# SCH_GloK_easyeda.net
KiCad netlist of a schematic drawn in EasyEDA
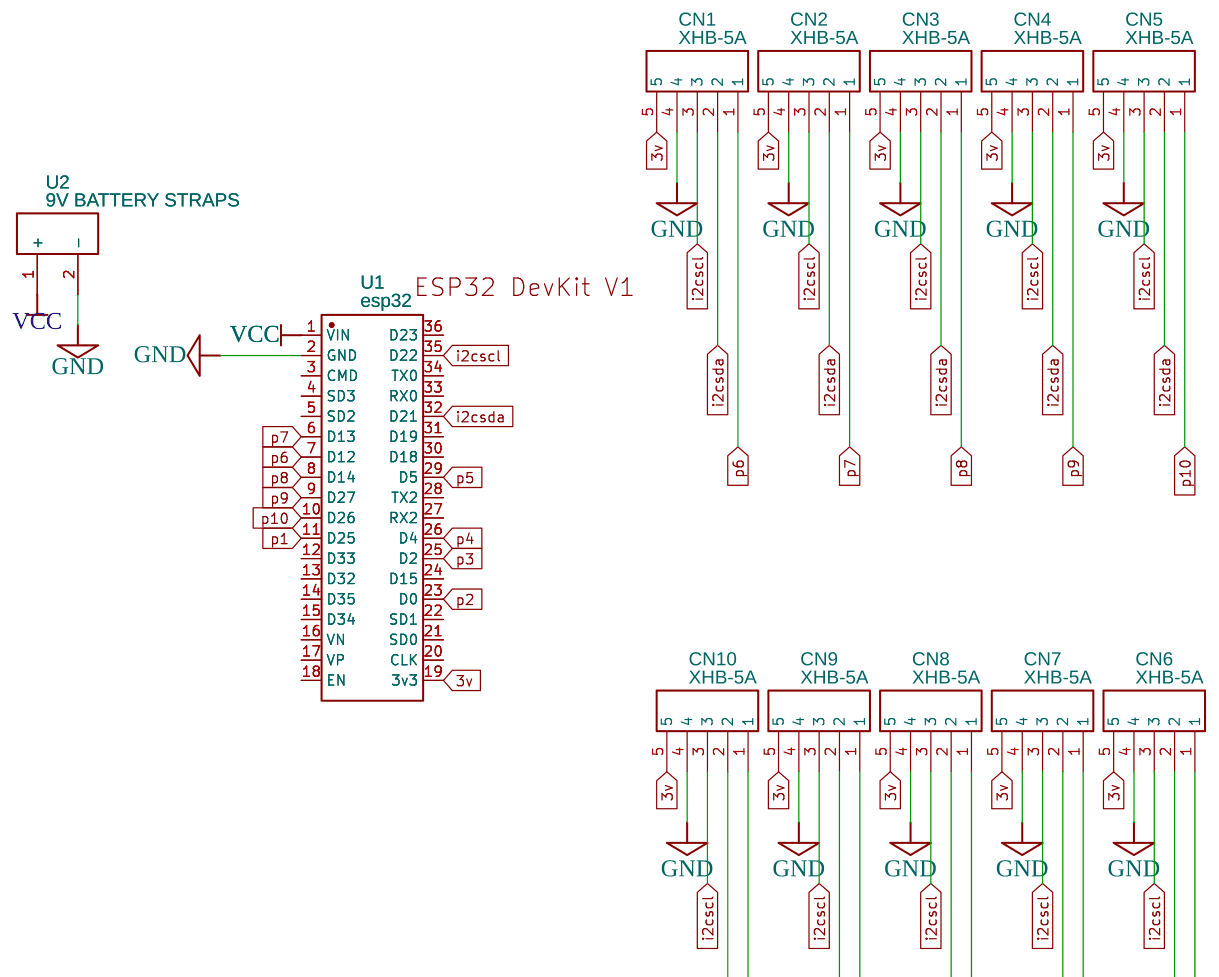
[diagram p0: schematic sheet]

(export (version "E")
  (design (tool "Eeschema 10.0.6"))
  (components
    (comp (ref "CN1")
      (value "XHB-5A")
      (fields (field (name "BOM_Supplier Part") "C66559"))
      (libsource (lib "") (part "XHB-5A"))
    )
    (comp (ref "CN2")
      (value "XHB-5A")
      (fields (field (name "BOM_Supplier Part") "C66559"))
      (libsource (lib "") (part "XHB-5A"))
    )
    (comp (ref "CN3")
      (value "XHB-5A")
      (fields (field (name "BOM_Supplier Part") "C66559"))
      (libsource (lib "") (part "XHB-5A"))
    )
    (comp (ref "CN4")
      (value "XHB-5A")
      (fields (field (name "BOM_Supplier Part") "C66559"))
      (libsource (lib "") (part "XHB-5A"))
    )
    (comp (ref "CN5")
      (value "XHB-5A")
      (fields (field (name "BOM_Supplier Part") "C66559"))
      (libsource (lib "") (part "XHB-5A"))
    )
    (comp (ref "CN6")
      (value "XHB-5A")
      (fields (field (name "BOM_Supplier Part") "C66559"))
      (libsource (lib "") (part "XHB-5A"))
    )
    (comp (ref "CN7")
      (value "XHB-5A")
      (fields (field (name "BOM_Supplier Part") "C66559"))
      (libsource (lib "") (part "XHB-5A"))
    )
    (comp (ref "CN8")
      (value "XHB-5A")
      (fields (field (name "BOM_Supplier Part") "C66559"))
      (libsource (lib "") (part "XHB-5A"))
    )
    (comp (ref "CN9")
      (value "XHB-5A")
      (fields (field (name "BOM_Supplier Part") "C66559"))
      (libsource (lib "") (part "XHB-5A"))
    )
    (comp (ref "CN10")
      (value "XHB-5A")
      (fields (field (name "BOM_Supplier Part") "C66559"))
      (libsource (lib "") (part "XHB-5A"))
    )
    (comp (ref "U1")
      (value "esp32")
      (fields (field (name "BOM_Supplier Part") "ESP32"))
      (libsource (lib "") (part "esp32"))
    )
    (comp (ref "U2")
      (value "9V BATTERY STRAPS")
      (fields (field (name "BOM_Manufacturer Part") "233") (field (name "BOM_Supplier Part") "36-233-ND"))
      (libsource (lib "") (part "9V BATTERY STRAPS"))
    )
  )
  (nets
    (net (code "1") (name "3v") (class "Default")
      (node (ref "CN1") (pin "5") (pinfunction "5_5") (pintype "unspecified"))
      (node (ref "CN10") (pin "5") (pinfunction "5_5") (pintype "unspecified"))
      (node (ref "CN2") (pin "5") (pinfunction "5_5") (pintype "unspecified"))
      (node (ref "CN3") (pin "5") (pinfunction "5_5") (pintype "unspecified"))
      (node (ref "CN4") (pin "5") (pinfunction "5_5") (pintype "unspecified"))
      (node (ref "CN5") (pin "5") (pinfunction "5_5") (pintype "unspecified"))
      (node (ref "CN6") (pin "5") (pinfunction "5_5") (pintype "unspecified"))
      (node (ref "CN7") (pin "5") (pinfunction "5_5") (pintype "unspecified"))
      (node (ref "CN8") (pin "5") (pinfunction "5_5") (pintype "unspecified"))
      (node (ref "CN9") (pin "5") (pinfunction "5_5") (pintype "unspecified"))
      (node (ref "U1") (pin "19") (pinfunction "3v3_19") (pintype "unspecified"))
    )
    (net (code "2") (name "GND") (class "Default")
      (node (ref "CN1") (pin "4") (pinfunction "4_4") (pintype "unspecified"))
      (node (ref "CN10") (pin "4") (pinfunction "4_4") (pintype "unspecified"))
      (node (ref "CN2") (pin "4") (pinfunction "4_4") (pintype "unspecified"))
      (node (ref "CN3") (pin "4") (pinfunction "4_4") (pintype "unspecified"))
      (node (ref "CN4") (pin "4") (pinfunction "4_4") (pintype "unspecified"))
      (node (ref "CN5") (pin "4") (pinfunction "4_4") (pintype "unspecified"))
      (node (ref "CN6") (pin "4") (pinfunction "4_4") (pintype "unspecified"))
      (node (ref "CN7") (pin "4") (pinfunction "4_4") (pintype "unspecified"))
      (node (ref "CN8") (pin "4") (pinfunction "4_4") (pintype "unspecified"))
      (node (ref "CN9") (pin "4") (pinfunction "4_4") (pintype "unspecified"))
      (node (ref "U1") (pin "2") (pinfunction "GND_2") (pintype "unspecified"))
      (node (ref "U2") (pin "2") (pinfunction "-_2") (pintype "unspecified"))
    )
    (net (code "3") (name "VCC") (class "Default")
      (node (ref "U1") (pin "1") (pinfunction "VIN_1") (pintype "unspecified"))
      (node (ref "U2") (pin "1") (pinfunction "+_1") (pintype "unspecified"))
    )
    (net (code "4") (name "i2cscl") (class "Default")
      (node (ref "CN1") (pin "3") (pinfunction "3_3") (pintype "unspecified"))
      (node (ref "CN10") (pin "3") (pinfunction "3_3") (pintype "unspecified"))
      (node (ref "CN2") (pin "3") (pinfunction "3_3") (pintype "unspecified"))
      (node (ref "CN3") (pin "3") (pinfunction "3_3") (pintype "unspecified"))
      (node (ref "CN4") (pin "3") (pinfunction "3_3") (pintype "unspecified"))
      (node (ref "CN5") (pin "3") (pinfunction "3_3") (pintype "unspecified"))
      (node (ref "CN6") (pin "3") (pinfunction "3_3") (pintype "unspecified"))
      (node (ref "CN7") (pin "3") (pinfunction "3_3") (pintype "unspecified"))
      (node (ref "CN8") (pin "3") (pinfunction "3_3") (pintype "unspecified"))
      (node (ref "CN9") (pin "3") (pinfunction "3_3") (pintype "unspecified"))
      (node (ref "U1") (pin "35") (pinfunction "D22_35") (pintype "unspecified"))
    )
    (net (code "5") (name "i2csda") (class "Default")
      (node (ref "CN1") (pin "2") (pinfunction "2_2") (pintype "unspecified"))
      (node (ref "CN10") (pin "2") (pinfunction "2_2") (pintype "unspecified"))
      (node (ref "CN2") (pin "2") (pinfunction "2_2") (pintype "unspecified"))
      (node (ref "CN3") (pin "2") (pinfunction "2_2") (pintype "unspecified"))
      (node (ref "CN4") (pin "2") (pinfunction "2_2") (pintype "unspecified"))
      (node (ref "CN5") (pin "2") (pinfunction "2_2") (pintype "unspecified"))
      (node (ref "CN6") (pin "2") (pinfunction "2_2") (pintype "unspecified"))
      (node (ref "CN7") (pin "2") (pinfunction "2_2") (pintype "unspecified"))
      (node (ref "CN8") (pin "2") (pinfunction "2_2") (pintype "unspecified"))
      (node (ref "CN9") (pin "2") (pinfunction "2_2") (pintype "unspecified"))
      (node (ref "U1") (pin "32") (pinfunction "D21_32") (pintype "unspecified"))
    )
    (net (code "6") (name "p1") (class "Default")
      (node (ref "CN10") (pin "1") (pinfunction "1_1") (pintype "unspecified"))
      (node (ref "U1") (pin "11") (pinfunction "D25_11") (pintype "unspecified"))
    )
    (net (code "7") (name "p2") (class "Default")
      (node (ref "CN9") (pin "1") (pinfunction "1_1") (pintype "unspecified"))
      (node (ref "U1") (pin "23") (pinfunction "D0_23") (pintype "unspecified"))
    )
    (net (code "8") (name "p3") (class "Default")
      (node (ref "CN8") (pin "1") (pinfunction "1_1") (pintype "unspecified"))
      (node (ref "U1") (pin "25") (pinfunction "D2_25") (pintype "unspecified"))
    )
    (net (code "9") (name "p4") (class "Default")
      (node (ref "CN7") (pin "1") (pinfunction "1_1") (pintype "unspecified"))
      (node (ref "U1") (pin "26") (pinfunction "D4_26") (pintype "unspecified"))
    )
    (net (code "10") (name "p5") (class "Default")
      (node (ref "CN6") (pin "1") (pinfunction "1_1") (pintype "unspecified"))
      (node (ref "U1") (pin "29") (pinfunction "D5_29") (pintype "unspecified"))
    )
    (net (code "11") (name "p6") (class "Default")
      (node (ref "CN1") (pin "1") (pinfunction "1_1") (pintype "unspecified"))
      (node (ref "U1") (pin "7") (pinfunction "D12_7") (pintype "unspecified"))
    )
    (net (code "12") (name "p7") (class "Default")
      (node (ref "CN2") (pin "1") (pinfunction "1_1") (pintype "unspecified"))
      (node (ref "U1") (pin "6") (pinfunction "D13_6") (pintype "unspecified"))
    )
    (net (code "13") (name "p8") (class "Default")
      (node (ref "CN3") (pin "1") (pinfunction "1_1") (pintype "unspecified"))
      (node (ref "U1") (pin "8") (pinfunction "D14_8") (pintype "unspecified"))
    )
    (net (code "14") (name "p9") (class "Default")
      (node (ref "CN4") (pin "1") (pinfunction "1_1") (pintype "unspecified"))
      (node (ref "U1") (pin "9") (pinfunction "D27_9") (pintype "unspecified"))
    )
    (net (code "15") (name "p10") (class "Default")
      (node (ref "CN5") (pin "1") (pinfunction "1_1") (pintype "unspecified"))
      (node (ref "U1") (pin "10") (pinfunction "D26_10") (pintype "unspecified"))
    )
    (net (code "16") (name "unconnected-(U1-CLK-Pad20)") (class "Default")
      (node (ref "U1") (pin "20") (pinfunction "CLK_20") (pintype "unspecified"))
    )
    (net (code "17") (name "unconnected-(U1-CMD-Pad3)") (class "Default")
      (node (ref "U1") (pin "3") (pinfunction "CMD_3") (pintype "unspecified"))
    )
    (net (code "18") (name "unconnected-(U1-D15-Pad24)") (class "Default")
      (node (ref "U1") (pin "24") (pinfunction "D15_24") (pintype "unspecified"))
    )
    (net (code "19") (name "unconnected-(U1-D18-Pad30)") (class "Default")
      (node (ref "U1") (pin "30") (pinfunction "D18_30") (pintype "unspecified"))
    )
    (net (code "20") (name "unconnected-(U1-D19-Pad31)") (class "Default")
      (node (ref "U1") (pin "31") (pinfunction "D19_31") (pintype "unspecified"))
    )
    (net (code "21") (name "unconnected-(U1-D23-Pad36)") (class "Default")
      (node (ref "U1") (pin "36") (pinfunction "D23_36") (pintype "unspecified"))
    )
    (net (code "22") (name "unconnected-(U1-D32-Pad13)") (class "Default")
      (node (ref "U1") (pin "13") (pinfunction "D32_13") (pintype "unspecified"))
    )
    (net (code "23") (name "unconnected-(U1-D33-Pad12)") (class "Default")
      (node (ref "U1") (pin "12") (pinfunction "D33_12") (pintype "unspecified"))
    )
    (net (code "24") (name "unconnected-(U1-D34-Pad15)") (class "Default")
      (node (ref "U1") (pin "15") (pinfunction "D34_15") (pintype "unspecified"))
    )
    (net (code "25") (name "unconnected-(U1-D35-Pad14)") (class "Default")
      (node (ref "U1") (pin "14") (pinfunction "D35_14") (pintype "unspecified"))
    )
    (net (code "26") (name "unconnected-(U1-EN-Pad18)") (class "Default")
      (node (ref "U1") (pin "18") (pinfunction "EN_18") (pintype "unspecified"))
    )
    (net (code "27") (name "unconnected-(U1-RX0-Pad33)") (class "Default")
      (node (ref "U1") (pin "33") (pinfunction "RX0_33") (pintype "unspecified"))
    )
    (net (code "28") (name "unconnected-(U1-RX2-Pad27)") (class "Default")
      (node (ref "U1") (pin "27") (pinfunction "RX2_27") (pintype "unspecified"))
    )
    (net (code "29") (name "unconnected-(U1-SD0-Pad21)") (class "Default")
      (node (ref "U1") (pin "21") (pinfunction "SD0_21") (pintype "unspecified"))
    )
    (net (code "30") (name "unconnected-(U1-SD1-Pad22)") (class "Default")
      (node (ref "U1") (pin "22") (pinfunction "SD1_22") (pintype "unspecified"))
    )
    (net (code "31") (name "unconnected-(U1-SD2-Pad5)") (class "Default")
      (node (ref "U1") (pin "5") (pinfunction "SD2_5") (pintype "unspecified"))
    )
    (net (code "32") (name "unconnected-(U1-SD3-Pad4)") (class "Default")
      (node (ref "U1") (pin "4") (pinfunction "SD3_4") (pintype "unspecified"))
    )
    (net (code "33") (name "unconnected-(U1-TX0-Pad34)") (class "Default")
      (node (ref "U1") (pin "34") (pinfunction "TX0_34") (pintype "unspecified"))
    )
    (net (code "34") (name "unconnected-(U1-TX2-Pad28)") (class "Default")
      (node (ref "U1") (pin "28") (pinfunction "TX2_28") (pintype "unspecified"))
    )
    (net (code "35") (name "unconnected-(U1-VN-Pad16)") (class "Default")
      (node (ref "U1") (pin "16") (pinfunction "VN_16") (pintype "unspecified"))
    )
    (net (code "36") (name "unconnected-(U1-VP-Pad17)") (class "Default")
      (node (ref "U1") (pin "17") (pinfunction "VP_17") (pintype "unspecified"))
    )
  )
)
